# AudioADC.net
KiCad netlist of a schematic drawn in Altium Designer
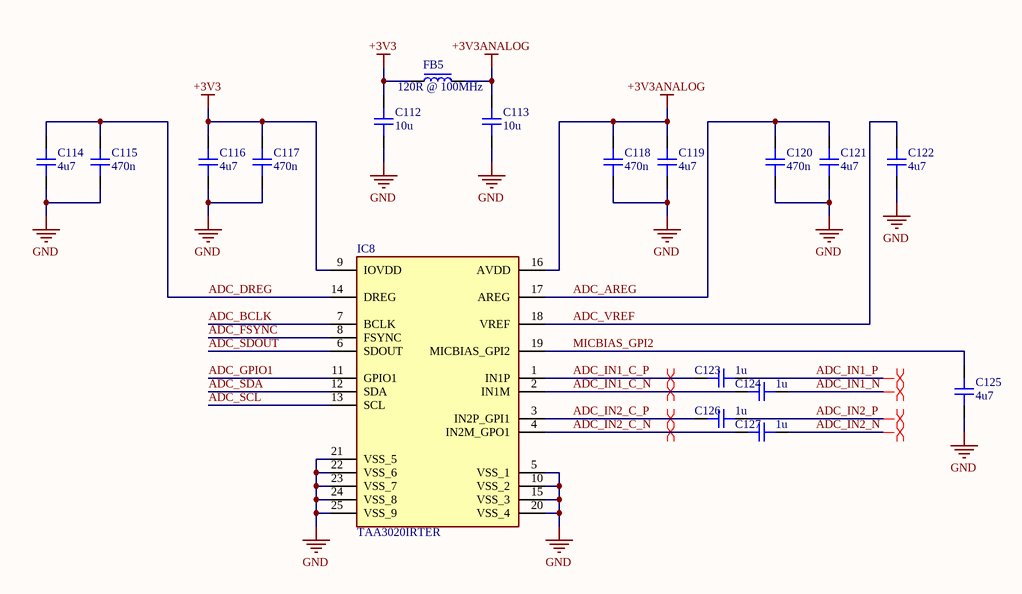
[diagram p0: AudioADC.SchDoc]

(export (version "E")
  (design (tool "Eeschema 10.0.6"))
  (components
    (comp (ref "C112")
      (value "10u")
      (footprint "CAP_0805")
      (description "Capacitor SMD 0805")
      (libsource (lib "Schematic-Lib-PhilsLab") (part "CAP_0805"))
    )
    (comp (ref "C113")
      (value "10u")
      (footprint "CAP_0805")
      (description "Capacitor SMD 0805")
      (libsource (lib "Schematic-Lib-PhilsLab") (part "CAP_0805"))
    )
    (comp (ref "C114")
      (value "4u7")
      (footprint "CAP_0402")
      (description "Capacitor SMD 0402")
      (libsource (lib "Schematic-Lib-PhilsLab") (part "CAP_0402"))
    )
    (comp (ref "C115")
      (value "470n")
      (footprint "CAP_0201")
      (description "Capacitor SMD 0201")
      (libsource (lib "Schematic-Lib-PhilsLab") (part "CAP_0201"))
    )
    (comp (ref "C116")
      (value "4u7")
      (footprint "CAP_0402")
      (description "Capacitor SMD 0402")
      (libsource (lib "Schematic-Lib-PhilsLab") (part "CAP_0402"))
    )
    (comp (ref "C117")
      (value "470n")
      (footprint "CAP_0201")
      (description "Capacitor SMD 0201")
      (libsource (lib "Schematic-Lib-PhilsLab") (part "CAP_0201"))
    )
    (comp (ref "C118")
      (value "470n")
      (footprint "CAP_0201")
      (description "Capacitor SMD 0201")
      (libsource (lib "Schematic-Lib-PhilsLab") (part "CAP_0201"))
    )
    (comp (ref "C119")
      (value "4u7")
      (footprint "CAP_0402")
      (description "Capacitor SMD 0402")
      (libsource (lib "Schematic-Lib-PhilsLab") (part "CAP_0402"))
    )
    (comp (ref "C120")
      (value "470n")
      (footprint "CAP_0201")
      (description "Capacitor SMD 0201")
      (libsource (lib "Schematic-Lib-PhilsLab") (part "CAP_0201"))
    )
    (comp (ref "C121")
      (value "4u7")
      (footprint "CAP_0402")
      (description "Capacitor SMD 0402")
      (libsource (lib "Schematic-Lib-PhilsLab") (part "CAP_0402"))
    )
    (comp (ref "C122")
      (value "4u7")
      (footprint "CAP_0402")
      (description "Capacitor SMD 0402")
      (libsource (lib "Schematic-Lib-PhilsLab") (part "CAP_0402"))
    )
    (comp (ref "C123")
      (value "1u")
      (footprint "CAP_0402")
      (description "Capacitor SMD 0402")
      (libsource (lib "Schematic-Lib-PhilsLab") (part "CAP_0402"))
    )
    (comp (ref "C124")
      (value "1u")
      (footprint "CAP_0402")
      (description "Capacitor SMD 0402")
      (libsource (lib "Schematic-Lib-PhilsLab") (part "CAP_0402"))
    )
    (comp (ref "C125")
      (value "4u7")
      (footprint "CAP_0402")
      (description "Capacitor SMD 0402")
      (libsource (lib "Schematic-Lib-PhilsLab") (part "CAP_0402"))
    )
    (comp (ref "C126")
      (value "1u")
      (footprint "CAP_0402")
      (description "Capacitor SMD 0402")
      (libsource (lib "Schematic-Lib-PhilsLab") (part "CAP_0402"))
    )
    (comp (ref "C127")
      (value "1u")
      (footprint "CAP_0402")
      (description "Capacitor SMD 0402")
      (libsource (lib "Schematic-Lib-PhilsLab") (part "CAP_0402"))
    )
    (comp (ref "FB5")
      (value "120R @ 100MHz")
      (footprint "FB_0805")
      (description "Ferrite Bead SMD 0805")
      (libsource (lib "Schematic-Lib-PhilsLab") (part "FB_0805"))
    )
    (comp (ref "IC8")
      (value "TAA3020IRTER")
      (footprint "Footprint-Lib-PhilsLab:PCM1820IRTER")
      (description "Integrated Circuit")
      (libsource (lib "Schematic-Lib-PhilsLab") (part "TAA3020IRTER"))
    )
  )
  (nets
    (net (code "1") (name "+3V3") (class "Default")
      (node (ref "C112") (pin "2") (pinfunction "2_2") (pintype "passive"))
      (node (ref "C116") (pin "2") (pinfunction "2_2") (pintype "passive"))
      (node (ref "C117") (pin "2") (pinfunction "2_2") (pintype "passive"))
      (node (ref "FB5") (pin "1") (pinfunction "1_1") (pintype "passive"))
      (node (ref "IC8") (pin "9") (pinfunction "IOVDD_9") (pintype "passive"))
    )
    (net (code "2") (name "+3V3ANALOG") (class "Default")
      (node (ref "C113") (pin "2") (pinfunction "2_2") (pintype "passive"))
      (node (ref "C118") (pin "2") (pinfunction "2_2") (pintype "passive"))
      (node (ref "C119") (pin "2") (pinfunction "2_2") (pintype "passive"))
      (node (ref "FB5") (pin "2") (pinfunction "2_2") (pintype "passive"))
      (node (ref "IC8") (pin "16") (pinfunction "AVDD_16") (pintype "passive"))
    )
    (net (code "3") (name "/ADC_AREG") (class "Default")
      (node (ref "C120") (pin "2") (pinfunction "2_2") (pintype "passive"))
      (node (ref "C121") (pin "2") (pinfunction "2_2") (pintype "passive"))
      (node (ref "IC8") (pin "17") (pinfunction "AREG_17") (pintype "passive"))
    )
    (net (code "4") (name "/ADC_BCLK") (class "Default")
      (node (ref "IC8") (pin "7") (pinfunction "BCLK_7") (pintype "passive"))
    )
    (net (code "5") (name "/ADC_DREG") (class "Default")
      (node (ref "C114") (pin "2") (pinfunction "2_2") (pintype "passive"))
      (node (ref "C115") (pin "2") (pinfunction "2_2") (pintype "passive"))
      (node (ref "IC8") (pin "14") (pinfunction "DREG_14") (pintype "passive"))
    )
    (net (code "6") (name "/ADC_FSYNC") (class "Default")
      (node (ref "IC8") (pin "8") (pinfunction "FSYNC_8") (pintype "passive"))
    )
    (net (code "7") (name "/ADC_GPIO1") (class "Default")
      (node (ref "IC8") (pin "11") (pinfunction "GPIO1_11") (pintype "passive"))
    )
    (net (code "8") (name "/ADC_IN1_C_N") (class "Default")
      (node (ref "C124") (pin "1") (pinfunction "1_1") (pintype "passive"))
      (node (ref "IC8") (pin "2") (pinfunction "IN1M_2") (pintype "passive"))
    )
    (net (code "9") (name "/ADC_IN1_C_P") (class "Default")
      (node (ref "C123") (pin "1") (pinfunction "1_1") (pintype "passive"))
      (node (ref "IC8") (pin "1") (pinfunction "IN1P_1") (pintype "passive"))
    )
    (net (code "10") (name "/ADC_IN1_N") (class "Default")
      (node (ref "C124") (pin "2") (pinfunction "2_2") (pintype "passive"))
    )
    (net (code "11") (name "/ADC_IN1_P") (class "Default")
      (node (ref "C123") (pin "2") (pinfunction "2_2") (pintype "passive"))
    )
    (net (code "12") (name "/ADC_IN2_C_N") (class "Default")
      (node (ref "C127") (pin "1") (pinfunction "1_1") (pintype "passive"))
      (node (ref "IC8") (pin "4") (pinfunction "IN2M_GPO1_4") (pintype "passive"))
    )
    (net (code "13") (name "/ADC_IN2_C_P") (class "Default")
      (node (ref "C126") (pin "1") (pinfunction "1_1") (pintype "passive"))
      (node (ref "IC8") (pin "3") (pinfunction "IN2P_GPI1_3") (pintype "passive"))
    )
    (net (code "14") (name "/ADC_IN2_N") (class "Default")
      (node (ref "C127") (pin "2") (pinfunction "2_2") (pintype "passive"))
    )
    (net (code "15") (name "/ADC_IN2_P") (class "Default")
      (node (ref "C126") (pin "2") (pinfunction "2_2") (pintype "passive"))
    )
    (net (code "16") (name "/ADC_SCL") (class "Default")
      (node (ref "IC8") (pin "13") (pinfunction "SCL_13") (pintype "passive"))
    )
    (net (code "17") (name "/ADC_SDA") (class "Default")
      (node (ref "IC8") (pin "12") (pinfunction "SDA_12") (pintype "passive"))
    )
    (net (code "18") (name "/ADC_SDOUT") (class "Default")
      (node (ref "IC8") (pin "6") (pinfunction "SDOUT_6") (pintype "passive"))
    )
    (net (code "19") (name "/ADC_VREF") (class "Default")
      (node (ref "C122") (pin "2") (pinfunction "2_2") (pintype "passive"))
      (node (ref "IC8") (pin "18") (pinfunction "VREF_18") (pintype "passive"))
    )
    (net (code "20") (name "/MICBIAS_GPI2") (class "Default")
      (node (ref "C125") (pin "2") (pinfunction "2_2") (pintype "passive"))
      (node (ref "IC8") (pin "19") (pinfunction "MICBIAS_GPI2_19") (pintype "passive"))
    )
    (net (code "21") (name "GND") (class "Default")
      (node (ref "C112") (pin "1") (pinfunction "1_1") (pintype "passive"))
      (node (ref "C113") (pin "1") (pinfunction "1_1") (pintype "passive"))
      (node (ref "C114") (pin "1") (pinfunction "1_1") (pintype "passive"))
      (node (ref "C115") (pin "1") (pinfunction "1_1") (pintype "passive"))
      (node (ref "C116") (pin "1") (pinfunction "1_1") (pintype "passive"))
      (node (ref "C117") (pin "1") (pinfunction "1_1") (pintype "passive"))
      (node (ref "C118") (pin "1") (pinfunction "1_1") (pintype "passive"))
      (node (ref "C119") (pin "1") (pinfunction "1_1") (pintype "passive"))
      (node (ref "C120") (pin "1") (pinfunction "1_1") (pintype "passive"))
      (node (ref "C121") (pin "1") (pinfunction "1_1") (pintype "passive"))
      (node (ref "C122") (pin "1") (pinfunction "1_1") (pintype "passive"))
      (node (ref "C125") (pin "1") (pinfunction "1_1") (pintype "passive"))
      (node (ref "IC8") (pin "10") (pinfunction "VSS_2_10") (pintype "passive"))
      (node (ref "IC8") (pin "15") (pinfunction "VSS_3_15") (pintype "passive"))
      (node (ref "IC8") (pin "20") (pinfunction "VSS_4_20") (pintype "passive"))
      (node (ref "IC8") (pin "21") (pinfunction "VSS_5_21") (pintype "passive"))
      (node (ref "IC8") (pin "22") (pinfunction "VSS_6_22") (pintype "passive"))
      (node (ref "IC8") (pin "23") (pinfunction "VSS_7_23") (pintype "passive"))
      (node (ref "IC8") (pin "24") (pinfunction "VSS_8_24") (pintype "passive"))
      (node (ref "IC8") (pin "25") (pinfunction "VSS_9_25") (pintype "passive"))
      (node (ref "IC8") (pin "5") (pinfunction "VSS_1_5") (pintype "passive"))
    )
  )
)
